# ecg-schematic.net
KiCad netlist of a schematic drawn in EAGLE
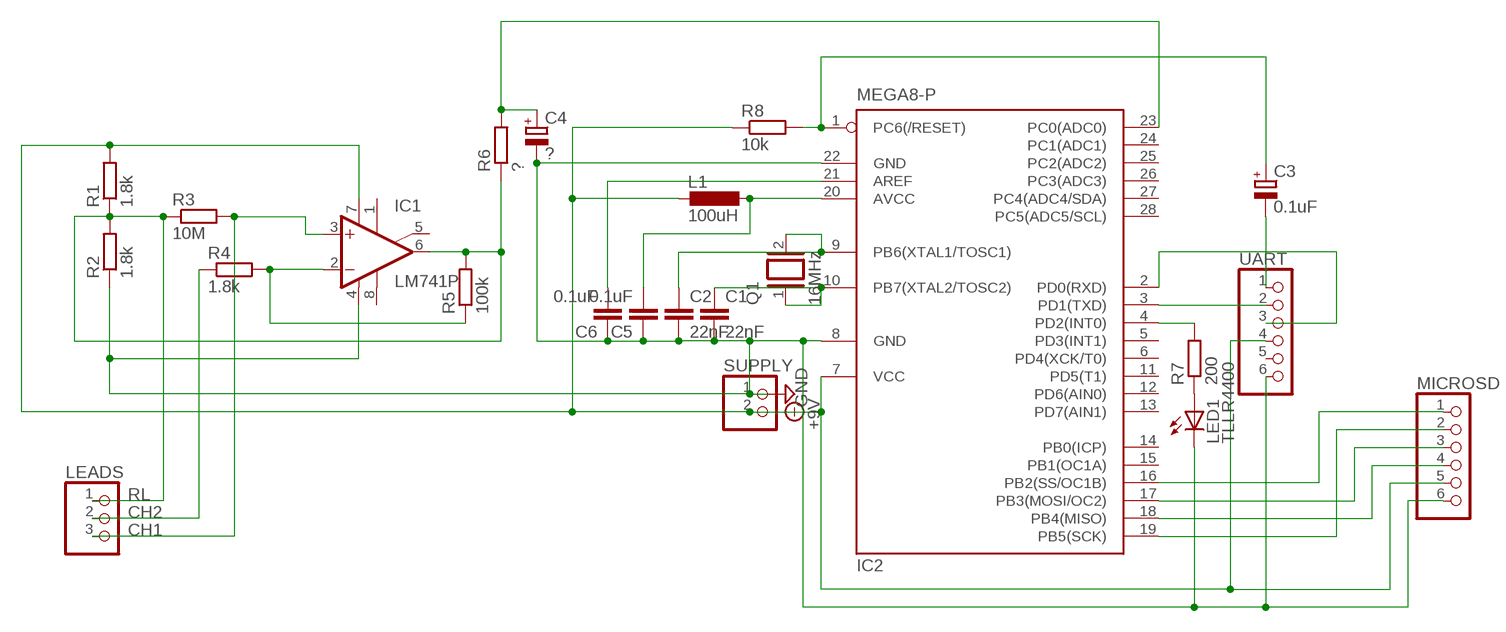
[diagram p0: schematic, sheet 1]

(export (version "E")
  (design (tool "Eeschema 10.0.6"))
  (components
    (comp (ref "C1")
      (value "22nF")
      (footprint "eagle-import:C025-025X050")
      (libsource (lib "eagle-import") (part "C-EU025-025X050"))
    )
    (comp (ref "C2")
      (value "22nF")
      (footprint "eagle-import:C025-025X050")
      (libsource (lib "eagle-import") (part "C-EU025-025X050"))
    )
    (comp (ref "C3")
      (value "0.1uF")
      (footprint "eagle-import:B45181A")
      (libsource (lib "eagle-import") (part "CPOL-EUB45181A"))
    )
    (comp (ref "C4")
      (value "?")
      (footprint "eagle-import:ETR1")
      (libsource (lib "eagle-import") (part "CPOL-EUETR1"))
    )
    (comp (ref "C5")
      (value "0.1uF")
      (footprint "eagle-import:C025-025X050")
      (libsource (lib "eagle-import") (part "C-EU025-025X050"))
    )
    (comp (ref "C6")
      (value "0.1uF")
      (footprint "eagle-import:C025-025X050")
      (libsource (lib "eagle-import") (part "C-EU025-025X050"))
    )
    (comp (ref "IC1")
      (value "LM741P")
      (footprint "eagle-import:DIL08")
      (libsource (lib "eagle-import") (part "741PLM"))
    )
    (comp (ref "IC2")
      (value "MEGA8-P")
      (footprint "eagle-import:DIL28-3")
      (libsource (lib "eagle-import") (part "MEGA8-P"))
    )
    (comp (ref "L1")
      (value "100uH")
      (footprint "eagle-import:0204_5")
      (libsource (lib "eagle-import") (part "L-EU0204/5"))
    )
    (comp (ref "LEADS")
      (value "PINHD-1X3")
      (footprint "eagle-import:1X03")
      (libsource (lib "eagle-import") (part "PINHD-1X3"))
    )
    (comp (ref "LED1")
      (value "TLLR4400")
      (footprint "eagle-import:LED3MM")
      (fields (field (name "MF") "VISHAY SEMICONDUCTOR"))
      (libsource (lib "eagle-import") (part "TLLR4400"))
    )
    (comp (ref "MICROSD")
      (value "PINHD-1X6")
      (footprint "eagle-import:1X06")
      (libsource (lib "eagle-import") (part "PINHD-1X6"))
    )
    (comp (ref "Q1")
      (value "16MHz")
      (footprint "eagle-import:QS")
      (libsource (lib "eagle-import") (part "XTAL/S"))
    )
    (comp (ref "R1")
      (value "1.8k")
      (footprint "eagle-import:0204_7")
      (libsource (lib "eagle-import") (part "R-EU_0204/7"))
    )
    (comp (ref "R2")
      (value "1.8k")
      (footprint "eagle-import:0204_7")
      (libsource (lib "eagle-import") (part "R-EU_0204/7"))
    )
    (comp (ref "R3")
      (value "10M")
      (footprint "eagle-import:0204_7")
      (libsource (lib "eagle-import") (part "R-EU_0204/7"))
    )
    (comp (ref "R4")
      (value "1.8k")
      (footprint "eagle-import:0204_7")
      (libsource (lib "eagle-import") (part "R-EU_0204/7"))
    )
    (comp (ref "R5")
      (value "100k")
      (footprint "eagle-import:0204_7")
      (libsource (lib "eagle-import") (part "R-EU_0204/7"))
    )
    (comp (ref "R6")
      (value "?")
      (footprint "eagle-import:0204_7")
      (libsource (lib "eagle-import") (part "R-EU_0204/7"))
    )
    (comp (ref "R7")
      (value "200")
      (footprint "eagle-import:0204_7")
      (libsource (lib "eagle-import") (part "R-EU_0204/7"))
    )
    (comp (ref "R8")
      (value "10k")
      (footprint "eagle-import:0204_7")
      (libsource (lib "eagle-import") (part "R-EU_0204/7"))
    )
    (comp (ref "SUPPLY")
      (value "PINHD-1X2")
      (footprint "eagle-import:1X02")
      (libsource (lib "eagle-import") (part "PINHD-1X2"))
    )
    (comp (ref "UART")
      (value "PINHD-1X6")
      (footprint "eagle-import:1X06")
      (libsource (lib "eagle-import") (part "PINHD-1X6"))
    )
  )
  (nets
    (net (code "1") (name "+9V") (class "Default")
      (node (ref "IC1") (pin "7") (pinfunction "V+_7") (pintype "power_in"))
      (node (ref "IC2") (pin "7") (pinfunction "VCC_7") (pintype "power_in"))
      (node (ref "L1") (pin "2") (pinfunction "2_2") (pintype "passive"))
      (node (ref "MICROSD") (pin "5") (pinfunction "5_5") (pintype "passive"))
      (node (ref "R1") (pin "2") (pinfunction "2_2") (pintype "passive"))
      (node (ref "R8") (pin "1") (pinfunction "1_1") (pintype "passive"))
      (node (ref "SUPPLY") (pin "2") (pinfunction "2_2") (pintype "passive"))
      (node (ref "UART") (pin "4") (pinfunction "4_4") (pintype "passive"))
    )
    (net (code "2") (name "/CH1") (class "Default")
      (node (ref "IC1") (pin "3") (pinfunction "+IN_3") (pintype "input"))
      (node (ref "LEADS") (pin "3") (pinfunction "3_3") (pintype "passive"))
      (node (ref "R3") (pin "2") (pinfunction "2_2") (pintype "passive"))
    )
    (net (code "3") (name "/CH2") (class "Default")
      (node (ref "LEADS") (pin "2") (pinfunction "2_2") (pintype "passive"))
      (node (ref "R4") (pin "1") (pinfunction "1_1") (pintype "passive"))
    )
    (net (code "4") (name "/RL") (class "Default")
      (node (ref "IC1") (pin "6") (pinfunction "OUT_6") (pintype "output"))
      (node (ref "LEADS") (pin "1") (pinfunction "1_1") (pintype "passive"))
      (node (ref "R1") (pin "1") (pinfunction "1_1") (pintype "passive"))
      (node (ref "R2") (pin "2") (pinfunction "2_2") (pintype "passive"))
      (node (ref "R3") (pin "1") (pinfunction "1_1") (pintype "passive"))
      (node (ref "R5") (pin "2") (pinfunction "2_2") (pintype "passive"))
      (node (ref "R6") (pin "1") (pinfunction "1_1") (pintype "passive"))
    )
    (net (code "5") (name "GND") (class "Default")
      (node (ref "C1") (pin "2") (pinfunction "2_2") (pintype "passive"))
      (node (ref "C2") (pin "2") (pinfunction "2_2") (pintype "passive"))
      (node (ref "C4") (pin "-") (pinfunction "-_-") (pintype "passive"))
      (node (ref "C5") (pin "1") (pinfunction "1_1") (pintype "passive"))
      (node (ref "C6") (pin "1") (pinfunction "1_1") (pintype "passive"))
      (node (ref "IC1") (pin "4") (pinfunction "V-_4") (pintype "power_in"))
      (node (ref "IC2") (pin "22") (pinfunction "GND_22") (pintype "power_in"))
      (node (ref "IC2") (pin "8") (pinfunction "GND_8") (pintype "power_in"))
      (node (ref "LED1") (pin "K") (pinfunction "C_K") (pintype "passive"))
      (node (ref "MICROSD") (pin "6") (pinfunction "6_6") (pintype "passive"))
      (node (ref "R2") (pin "1") (pinfunction "1_1") (pintype "passive"))
      (node (ref "SUPPLY") (pin "1") (pinfunction "1_1") (pintype "passive"))
      (node (ref "UART") (pin "6") (pinfunction "6_6") (pintype "passive"))
    )
    (net (code "6") (name "Net-(C3-Pad-)") (class "Default")
      (node (ref "C3") (pin "-") (pinfunction "-_-") (pintype "passive"))
      (node (ref "UART") (pin "1") (pinfunction "1_1") (pintype "passive"))
    )
    (net (code "7") (name "Net-(IC1--IN)") (class "Default")
      (node (ref "IC1") (pin "2") (pinfunction "-IN_2") (pintype "input"))
      (node (ref "R4") (pin "2") (pinfunction "2_2") (pintype "passive"))
      (node (ref "R5") (pin "1") (pinfunction "1_1") (pintype "passive"))
    )
    (net (code "8") (name "Net-(IC2-AREF)") (class "Default")
      (node (ref "C6") (pin "2") (pinfunction "2_2") (pintype "passive"))
      (node (ref "IC2") (pin "21") (pinfunction "AREF_21") (pintype "passive"))
    )
    (net (code "9") (name "Net-(IC2-AVCC)") (class "Default")
      (node (ref "C5") (pin "2") (pinfunction "2_2") (pintype "passive"))
      (node (ref "IC2") (pin "20") (pinfunction "AVCC_20") (pintype "power_in"))
      (node (ref "L1") (pin "1") (pinfunction "1_1") (pintype "passive"))
    )
    (net (code "10") (name "Net-(IC2-PB2(SS{slash}OC1B))") (class "Default")
      (node (ref "IC2") (pin "16") (pinfunction "PB2(SS/OC1B)_16") (pintype "bidirectional"))
      (node (ref "MICROSD") (pin "1") (pinfunction "1_1") (pintype "passive"))
    )
    (net (code "11") (name "Net-(IC2-PB3(MOSI{slash}OC2))") (class "Default")
      (node (ref "IC2") (pin "17") (pinfunction "PB3(MOSI/OC2)_17") (pintype "bidirectional"))
      (node (ref "MICROSD") (pin "3") (pinfunction "3_3") (pintype "passive"))
    )
    (net (code "12") (name "Net-(IC2-PB4(MISO))") (class "Default")
      (node (ref "IC2") (pin "18") (pinfunction "PB4(MISO)_18") (pintype "bidirectional"))
      (node (ref "MICROSD") (pin "4") (pinfunction "4_4") (pintype "passive"))
    )
    (net (code "13") (name "Net-(IC2-PB5(SCK))") (class "Default")
      (node (ref "IC2") (pin "19") (pinfunction "PB5(SCK)_19") (pintype "bidirectional"))
      (node (ref "MICROSD") (pin "2") (pinfunction "2_2") (pintype "passive"))
    )
    (net (code "14") (name "Net-(IC2-PB6(XTAL1{slash}TOSC1))") (class "Default")
      (node (ref "C2") (pin "1") (pinfunction "1_1") (pintype "passive"))
      (node (ref "IC2") (pin "9") (pinfunction "PB6(XTAL1/TOSC1)_9") (pintype "bidirectional"))
      (node (ref "Q1") (pin "2") (pinfunction "2_2") (pintype "passive"))
    )
    (net (code "15") (name "Net-(IC2-PB7(XTAL2{slash}TOSC2))") (class "Default")
      (node (ref "C1") (pin "1") (pinfunction "1_1") (pintype "passive"))
      (node (ref "IC2") (pin "10") (pinfunction "PB7(XTAL2/TOSC2)_10") (pintype "bidirectional"))
      (node (ref "Q1") (pin "1") (pinfunction "1_1") (pintype "passive"))
    )
    (net (code "16") (name "Net-(IC2-PC0(ADC0))") (class "Default")
      (node (ref "C4") (pin "+") (pinfunction "+_+") (pintype "passive"))
      (node (ref "IC2") (pin "23") (pinfunction "PC0(ADC0)_23") (pintype "bidirectional"))
      (node (ref "R6") (pin "2") (pinfunction "2_2") (pintype "passive"))
    )
    (net (code "17") (name "Net-(IC2-PC6({slash}RESET))") (class "Default")
      (node (ref "C3") (pin "+") (pinfunction "+_+") (pintype "passive"))
      (node (ref "IC2") (pin "1") (pinfunction "PC6(/RESET)_1") (pintype "bidirectional"))
      (node (ref "R8") (pin "2") (pinfunction "2_2") (pintype "passive"))
    )
    (net (code "18") (name "Net-(IC2-PD0(RXD))") (class "Default")
      (node (ref "IC2") (pin "2") (pinfunction "PD0(RXD)_2") (pintype "bidirectional"))
      (node (ref "UART") (pin "3") (pinfunction "3_3") (pintype "passive"))
    )
    (net (code "19") (name "Net-(IC2-PD1(TXD))") (class "Default")
      (node (ref "IC2") (pin "3") (pinfunction "PD1(TXD)_3") (pintype "bidirectional"))
      (node (ref "UART") (pin "2") (pinfunction "2_2") (pintype "passive"))
    )
    (net (code "20") (name "Net-(IC2-PD2(INT0))") (class "Default")
      (node (ref "IC2") (pin "4") (pinfunction "PD2(INT0)_4") (pintype "bidirectional"))
      (node (ref "R7") (pin "2") (pinfunction "2_2") (pintype "passive"))
    )
    (net (code "21") (name "Net-(LED1-PadA)") (class "Default")
      (node (ref "LED1") (pin "A") (pinfunction "A_A") (pintype "passive"))
      (node (ref "R7") (pin "1") (pinfunction "1_1") (pintype "passive"))
    )
    (net (code "22") (name "unconnected-(IC1-ON1-Pad1)") (class "Default")
      (node (ref "IC1") (pin "1") (pinfunction "ON1_1") (pintype "passive"))
    )
    (net (code "23") (name "unconnected-(IC1-ON2-Pad5)") (class "Default")
      (node (ref "IC1") (pin "5") (pinfunction "ON2_5") (pintype "passive"))
    )
    (net (code "24") (name "unconnected-(IC1-OPT-Pad8)") (class "Default")
      (node (ref "IC1") (pin "8") (pinfunction "OPT_8") (pintype "passive"))
    )
    (net (code "25") (name "unconnected-(IC2-PB0(ICP)-Pad14)") (class "Default")
      (node (ref "IC2") (pin "14") (pinfunction "PB0(ICP)_14") (pintype "bidirectional"))
    )
    (net (code "26") (name "unconnected-(IC2-PB1(OC1A)-Pad15)") (class "Default")
      (node (ref "IC2") (pin "15") (pinfunction "PB1(OC1A)_15") (pintype "bidirectional"))
    )
    (net (code "27") (name "unconnected-(IC2-PC1(ADC1)-Pad24)") (class "Default")
      (node (ref "IC2") (pin "24") (pinfunction "PC1(ADC1)_24") (pintype "bidirectional"))
    )
    (net (code "28") (name "unconnected-(IC2-PC2(ADC2)-Pad25)") (class "Default")
      (node (ref "IC2") (pin "25") (pinfunction "PC2(ADC2)_25") (pintype "bidirectional"))
    )
    (net (code "29") (name "unconnected-(IC2-PC3(ADC3)-Pad26)") (class "Default")
      (node (ref "IC2") (pin "26") (pinfunction "PC3(ADC3)_26") (pintype "bidirectional"))
    )
    (net (code "30") (name "unconnected-(IC2-PC4(ADC4{slash}SDA)-Pad27)") (class "Default")
      (node (ref "IC2") (pin "27") (pinfunction "PC4(ADC4/SDA)_27") (pintype "bidirectional"))
    )
    (net (code "31") (name "unconnected-(IC2-PC5(ADC5{slash}SCL)-Pad28)") (class "Default")
      (node (ref "IC2") (pin "28") (pinfunction "PC5(ADC5/SCL)_28") (pintype "bidirectional"))
    )
    (net (code "32") (name "unconnected-(IC2-PD3(INT1)-Pad5)") (class "Default")
      (node (ref "IC2") (pin "5") (pinfunction "PD3(INT1)_5") (pintype "bidirectional"))
    )
    (net (code "33") (name "unconnected-(IC2-PD4(XCK{slash}T0)-Pad6)") (class "Default")
      (node (ref "IC2") (pin "6") (pinfunction "PD4(XCK/T0)_6") (pintype "bidirectional"))
    )
    (net (code "34") (name "unconnected-(IC2-PD5(T1)-Pad11)") (class "Default")
      (node (ref "IC2") (pin "11") (pinfunction "PD5(T1)_11") (pintype "bidirectional"))
    )
    (net (code "35") (name "unconnected-(IC2-PD6(AIN0)-Pad12)") (class "Default")
      (node (ref "IC2") (pin "12") (pinfunction "PD6(AIN0)_12") (pintype "bidirectional"))
    )
    (net (code "36") (name "unconnected-(IC2-PD7(AIN1)-Pad13)") (class "Default")
      (node (ref "IC2") (pin "13") (pinfunction "PD7(AIN1)_13") (pintype "bidirectional"))
    )
    (net (code "37") (name "unconnected-(UART-Pad5)") (class "Default")
      (node (ref "UART") (pin "5") (pinfunction "5_5") (pintype "passive"))
    )
  )
)
